# MCU.net
KiCad netlist of a schematic drawn in Altium Designer
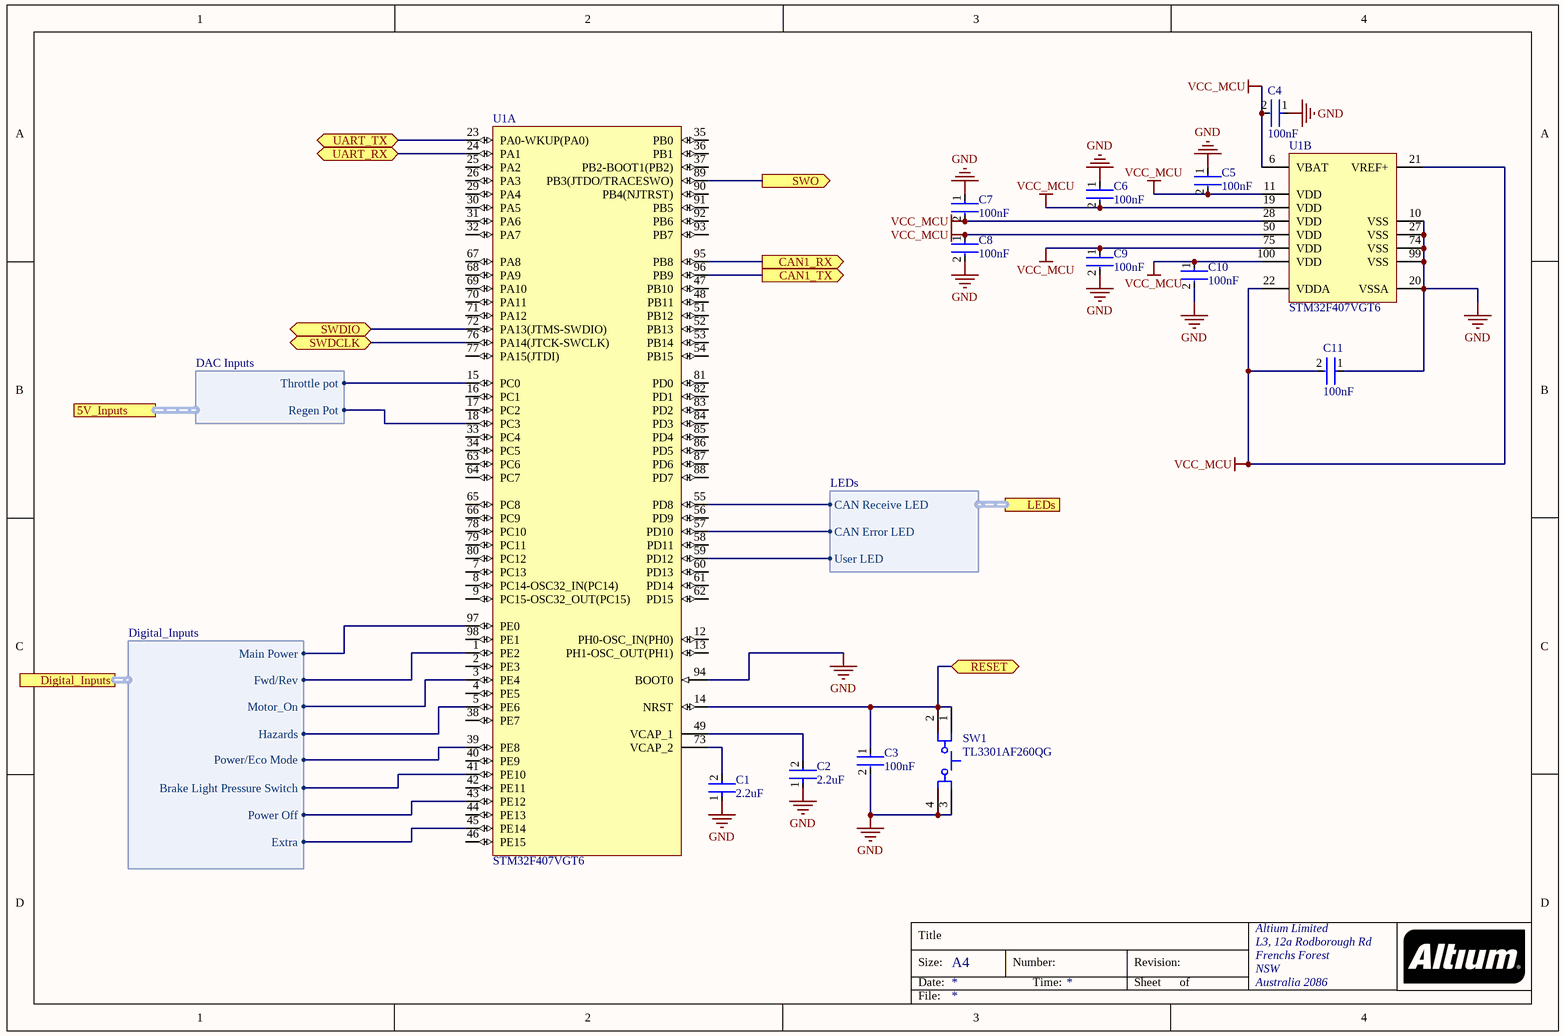
[diagram p0: MCU.SchDoc]

(export (version "E")
  (design (tool "Eeschema 10.0.6"))
  (components
    (comp (ref "C1")
      (value "2.2uF")
      (footprint "Yageo_CC0805-0.85_IPC_A")
      (description "2.2UF CC0805KKX7R6BB225")
      (libsource (lib "Cap_Yageo_CC0805KKX7R6BB225_eec") (part "CC0805KKX7R6BB225"))
    )
    (comp (ref "C2")
      (value "2.2uF")
      (footprint "Yageo_CC0805-0.85_IPC_A")
      (description "2.2UF CC0805KKX7R6BB225")
      (libsource (lib "Cap_Yageo_CC0805KKX7R6BB225_eec") (part "CC0805KKX7R6BB225"))
    )
    (comp (ref "C3")
      (value "100nF")
      (footprint "Kemet_C0603_IPC_A")
      (description "CAP CER 0.1UF 100NF 50V X7R 0603 C0603C104K5RACTU")
      (libsource (lib "UNK_Kemet_C0603C104K5RACTU_eec") (part "C0603C104K5RACTU"))
    )
    (comp (ref "C4")
      (value "100nF")
      (footprint "Kemet_C0603_IPC_A")
      (description "CAP CER 0.1UF 100NF 50V X7R 0603 C0603C104K5RACTU")
      (libsource (lib "UNK_Kemet_C0603C104K5RACTU_eec") (part "C0603C104K5RACTU"))
    )
    (comp (ref "C5")
      (value "100nF")
      (footprint "Kemet_C0603_IPC_A")
      (description "CAP CER 0.1UF 100NF 50V X7R 0603 C0603C104K5RACTU")
      (libsource (lib "UNK_Kemet_C0603C104K5RACTU_eec") (part "C0603C104K5RACTU"))
    )
    (comp (ref "C6")
      (value "100nF")
      (footprint "Kemet_C0603_IPC_A")
      (description "CAP CER 0.1UF 100NF 50V X7R 0603 C0603C104K5RACTU")
      (libsource (lib "UNK_Kemet_C0603C104K5RACTU_eec") (part "C0603C104K5RACTU"))
    )
    (comp (ref "C7")
      (value "100nF")
      (footprint "Kemet_C0603_IPC_A")
      (description "CAP CER 0.1UF 100NF 50V X7R 0603 C0603C104K5RACTU")
      (libsource (lib "UNK_Kemet_C0603C104K5RACTU_eec") (part "C0603C104K5RACTU"))
    )
    (comp (ref "C8")
      (value "100nF")
      (footprint "Kemet_C0603_IPC_A")
      (description "CAP CER 0.1UF 100NF 50V X7R 0603 C0603C104K5RACTU")
      (libsource (lib "UNK_Kemet_C0603C104K5RACTU_eec") (part "C0603C104K5RACTU"))
    )
    (comp (ref "C9")
      (value "100nF")
      (footprint "Kemet_C0603_IPC_A")
      (description "CAP CER 0.1UF 100NF 50V X7R 0603 C0603C104K5RACTU")
      (libsource (lib "UNK_Kemet_C0603C104K5RACTU_eec") (part "C0603C104K5RACTU"))
    )
    (comp (ref "C10")
      (value "100nF")
      (footprint "Kemet_C0603_IPC_A")
      (description "CAP CER 0.1UF 100NF 50V X7R 0603 C0603C104K5RACTU")
      (libsource (lib "UNK_Kemet_C0603C104K5RACTU_eec") (part "C0603C104K5RACTU"))
    )
    (comp (ref "C11")
      (value "100nF")
      (footprint "Kemet_C0603_IPC_A")
      (description "CAP CER 0.1UF 100NF 50V X7R 0603 C0603C104K5RACTU")
      (libsource (lib "UNK_Kemet_C0603C104K5RACTU_eec") (part "C0603C104K5RACTU"))
    )
    (comp (ref "SW1")
      (value "TL3301AF260QG")
      (footprint "ESWI-TL3301AF260QG_V")
      (description "Tactile Switch, SPST-NO, 50 mA, 12 V, -20 to 70 degC, 4-Pin SMD, RoHS, Tape and Reel")
      (fields (field (name "MANUFACTURER") "E-Switch"))
      (libsource (lib "Altium Content Vault") (part "SW-SPST-NO-4"))
    )
    (comp (ref "U1")
      (value "STM32F407VGT6")
      (footprint "STM-LQFP100_M")
      (fields (field (name "MANUFACTURER") "STMicroelectronics"))
      (libsource (lib "Altium Content Vault") (part "MC-ARM-STM32F40X_41X-SQ100"))
    )
  )
  (nets
    (net (code "5") (name "/Brake Light Pressure Switch") (class "Default")
      (node (ref "U1") (pin "41") (pinfunction "PE10_41") (pintype "bidirectional"))
    )
    (net (code "6") (name "/CAN Error LED") (class "Default")
      (node (ref "U1") (pin "57") (pinfunction "PD10_57") (pintype "bidirectional"))
    )
    (net (code "7") (name "/CAN Receive LED") (class "Default")
      (node (ref "U1") (pin "55") (pinfunction "PD8_55") (pintype "bidirectional"))
    )
    (net (code "8") (name "/CAN1_RX") (class "Default")
      (node (ref "U1") (pin "95") (pinfunction "PB8_95") (pintype "bidirectional"))
    )
    (net (code "9") (name "/CAN1_TX") (class "Default")
      (node (ref "U1") (pin "96") (pinfunction "PB9_96") (pintype "bidirectional"))
    )
    (net (code "10") (name "/Extra") (class "Default")
      (node (ref "U1") (pin "45") (pinfunction "PE14_45") (pintype "bidirectional"))
    )
    (net (code "11") (name "/Fwd{slash}Rev") (class "Default")
      (node (ref "U1") (pin "1") (pinfunction "PE2_1") (pintype "bidirectional"))
    )
    (net (code "12") (name "/Hazards") (class "Default")
      (node (ref "U1") (pin "5") (pinfunction "PE6_5") (pintype "bidirectional"))
    )
    (net (code "13") (name "/Main Power") (class "Default")
      (node (ref "U1") (pin "97") (pinfunction "PE0_97") (pintype "bidirectional"))
    )
    (net (code "14") (name "/Motor_On") (class "Default")
      (node (ref "U1") (pin "3") (pinfunction "PE4_3") (pintype "bidirectional"))
    )
    (net (code "15") (name "/Power Off") (class "Default")
      (node (ref "U1") (pin "43") (pinfunction "PE12_43") (pintype "bidirectional"))
    )
    (net (code "16") (name "/Power{slash}Eco Mode") (class "Default")
      (node (ref "U1") (pin "39") (pinfunction "PE8_39") (pintype "bidirectional"))
    )
    (net (code "17") (name "/RESET") (class "Default")
      (node (ref "C3") (pin "1") (pinfunction "1_1") (pintype "passive"))
      (node (ref "SW1") (pin "1") (pinfunction "1_1") (pintype "passive"))
      (node (ref "SW1") (pin "2") (pinfunction "2_2") (pintype "passive"))
      (node (ref "U1") (pin "14") (pinfunction "NRST_14") (pintype "bidirectional"))
    )
    (net (code "18") (name "/Regen Pot") (class "Default")
      (node (ref "U1") (pin "18") (pinfunction "PC3_18") (pintype "bidirectional"))
    )
    (net (code "19") (name "/SWDCLK") (class "Default")
      (node (ref "U1") (pin "76") (pinfunction "PA14(JTCK-SWCLK)_76") (pintype "bidirectional"))
    )
    (net (code "20") (name "/SWDIO") (class "Default")
      (node (ref "U1") (pin "72") (pinfunction "PA13(JTMS-SWDIO)_72") (pintype "bidirectional"))
    )
    (net (code "21") (name "/SWO") (class "Default")
      (node (ref "U1") (pin "89") (pinfunction "PB3(JTDO/TRACESWO)_89") (pintype "bidirectional"))
    )
    (net (code "22") (name "/Throttle pot") (class "Default")
      (node (ref "U1") (pin "15") (pinfunction "PC0_15") (pintype "bidirectional"))
    )
    (net (code "23") (name "/UART_RX") (class "Default")
      (node (ref "U1") (pin "24") (pinfunction "PA1_24") (pintype "bidirectional"))
    )
    (net (code "24") (name "/UART_TX") (class "Default")
      (node (ref "U1") (pin "23") (pinfunction "PA0-WKUP(PA0)_23") (pintype "bidirectional"))
    )
    (net (code "25") (name "/User LED") (class "Default")
      (node (ref "U1") (pin "59") (pinfunction "PD12_59") (pintype "bidirectional"))
    )
    (net (code "29") (name "GND") (class "Default")
      (node (ref "C1") (pin "1") (pinfunction "1_1") (pintype "passive"))
      (node (ref "C10") (pin "2") (pinfunction "2_2") (pintype "passive"))
      (node (ref "C11") (pin "1") (pinfunction "1_1") (pintype "passive"))
      (node (ref "C2") (pin "1") (pinfunction "1_1") (pintype "passive"))
      (node (ref "C3") (pin "2") (pinfunction "2_2") (pintype "passive"))
      (node (ref "C4") (pin "1") (pinfunction "1_1") (pintype "passive"))
      (node (ref "C5") (pin "1") (pinfunction "1_1") (pintype "passive"))
      (node (ref "C6") (pin "1") (pinfunction "1_1") (pintype "passive"))
      (node (ref "C7") (pin "1") (pinfunction "1_1") (pintype "passive"))
      (node (ref "C8") (pin "2") (pinfunction "2_2") (pintype "passive"))
      (node (ref "C9") (pin "2") (pinfunction "2_2") (pintype "passive"))
      (node (ref "SW1") (pin "3") (pinfunction "3_3") (pintype "passive"))
      (node (ref "SW1") (pin "4") (pinfunction "4_4") (pintype "passive"))
      (node (ref "U1") (pin "10") (pinfunction "VSS_10") (pintype "power_in"))
      (node (ref "U1") (pin "20") (pinfunction "VSSA_20") (pintype "power_in"))
      (node (ref "U1") (pin "27") (pinfunction "VSS_27") (pintype "power_in"))
      (node (ref "U1") (pin "74") (pinfunction "VSS_74") (pintype "power_in"))
      (node (ref "U1") (pin "94") (pinfunction "BOOT0_94") (pintype "input"))
      (node (ref "U1") (pin "99") (pinfunction "VSS_99") (pintype "power_in"))
    )
    (net (code "30") (name "Net-(U1A-VCAP_1)") (class "Default")
      (node (ref "C2") (pin "2") (pinfunction "2_2") (pintype "passive"))
      (node (ref "U1") (pin "49") (pinfunction "VCAP_1_49") (pintype "power_in"))
    )
    (net (code "31") (name "Net-(U1A-VCAP_2)") (class "Default")
      (node (ref "C1") (pin "2") (pinfunction "2_2") (pintype "passive"))
      (node (ref "U1") (pin "73") (pinfunction "VCAP_2_73") (pintype "power_in"))
    )
    (net (code "32") (name "VCC_MCU") (class "Default")
      (node (ref "C10") (pin "1") (pinfunction "1_1") (pintype "passive"))
      (node (ref "C11") (pin "2") (pinfunction "2_2") (pintype "passive"))
      (node (ref "C4") (pin "2") (pinfunction "2_2") (pintype "passive"))
      (node (ref "C5") (pin "2") (pinfunction "2_2") (pintype "passive"))
      (node (ref "C6") (pin "2") (pinfunction "2_2") (pintype "passive"))
      (node (ref "C7") (pin "2") (pinfunction "2_2") (pintype "passive"))
      (node (ref "C8") (pin "1") (pinfunction "1_1") (pintype "passive"))
      (node (ref "C9") (pin "1") (pinfunction "1_1") (pintype "passive"))
      (node (ref "U1") (pin "100") (pinfunction "VDD_100") (pintype "power_in"))
      (node (ref "U1") (pin "11") (pinfunction "VDD_11") (pintype "power_in"))
      (node (ref "U1") (pin "19") (pinfunction "VDD_19") (pintype "power_in"))
      (node (ref "U1") (pin "21") (pinfunction "VREF+_21") (pintype "power_in"))
      (node (ref "U1") (pin "22") (pinfunction "VDDA_22") (pintype "power_in"))
      (node (ref "U1") (pin "28") (pinfunction "VDD_28") (pintype "power_in"))
      (node (ref "U1") (pin "50") (pinfunction "VDD_50") (pintype "power_in"))
      (node (ref "U1") (pin "6") (pinfunction "VBAT_6") (pintype "power_in"))
      (node (ref "U1") (pin "75") (pinfunction "VDD_75") (pintype "power_in"))
    )
    (net (code "33") (name "unconnected-(U1A-PA2-Pad25)") (class "Default")
      (node (ref "U1") (pin "25") (pinfunction "PA2_25") (pintype "bidirectional"))
    )
    (net (code "34") (name "unconnected-(U1A-PA3-Pad26)") (class "Default")
      (node (ref "U1") (pin "26") (pinfunction "PA3_26") (pintype "bidirectional"))
    )
    (net (code "35") (name "unconnected-(U1A-PA4-Pad29)") (class "Default")
      (node (ref "U1") (pin "29") (pinfunction "PA4_29") (pintype "bidirectional"))
    )
    (net (code "36") (name "unconnected-(U1A-PA5-Pad30)") (class "Default")
      (node (ref "U1") (pin "30") (pinfunction "PA5_30") (pintype "bidirectional"))
    )
    (net (code "37") (name "unconnected-(U1A-PA6-Pad31)") (class "Default")
      (node (ref "U1") (pin "31") (pinfunction "PA6_31") (pintype "bidirectional"))
    )
    (net (code "38") (name "unconnected-(U1A-PA7-Pad32)") (class "Default")
      (node (ref "U1") (pin "32") (pinfunction "PA7_32") (pintype "bidirectional"))
    )
    (net (code "39") (name "unconnected-(U1A-PA8-Pad67)") (class "Default")
      (node (ref "U1") (pin "67") (pinfunction "PA8_67") (pintype "bidirectional"))
    )
    (net (code "40") (name "unconnected-(U1A-PA9-Pad68)") (class "Default")
      (node (ref "U1") (pin "68") (pinfunction "PA9_68") (pintype "bidirectional"))
    )
    (net (code "41") (name "unconnected-(U1A-PA10-Pad69)") (class "Default")
      (node (ref "U1") (pin "69") (pinfunction "PA10_69") (pintype "bidirectional"))
    )
    (net (code "42") (name "unconnected-(U1A-PA11-Pad70)") (class "Default")
      (node (ref "U1") (pin "70") (pinfunction "PA11_70") (pintype "bidirectional"))
    )
    (net (code "43") (name "unconnected-(U1A-PA12-Pad71)") (class "Default")
      (node (ref "U1") (pin "71") (pinfunction "PA12_71") (pintype "bidirectional"))
    )
    (net (code "44") (name "unconnected-(U1A-PA15(JTDI)-Pad77)") (class "Default")
      (node (ref "U1") (pin "77") (pinfunction "PA15(JTDI)_77") (pintype "bidirectional"))
    )
    (net (code "45") (name "unconnected-(U1A-PB0-Pad35)") (class "Default")
      (node (ref "U1") (pin "35") (pinfunction "PB0_35") (pintype "bidirectional"))
    )
    (net (code "46") (name "unconnected-(U1A-PB1-Pad36)") (class "Default")
      (node (ref "U1") (pin "36") (pinfunction "PB1_36") (pintype "bidirectional"))
    )
    (net (code "47") (name "unconnected-(U1A-PB2-BOOT1(PB2)-Pad37)") (class "Default")
      (node (ref "U1") (pin "37") (pinfunction "PB2-BOOT1(PB2)_37") (pintype "bidirectional"))
    )
    (net (code "48") (name "unconnected-(U1A-PB4(NJTRST)-Pad90)") (class "Default")
      (node (ref "U1") (pin "90") (pinfunction "PB4(NJTRST)_90") (pintype "bidirectional"))
    )
    (net (code "49") (name "unconnected-(U1A-PB5-Pad91)") (class "Default")
      (node (ref "U1") (pin "91") (pinfunction "PB5_91") (pintype "bidirectional"))
    )
    (net (code "50") (name "unconnected-(U1A-PB6-Pad92)") (class "Default")
      (node (ref "U1") (pin "92") (pinfunction "PB6_92") (pintype "bidirectional"))
    )
    (net (code "51") (name "unconnected-(U1A-PB7-Pad93)") (class "Default")
      (node (ref "U1") (pin "93") (pinfunction "PB7_93") (pintype "bidirectional"))
    )
    (net (code "52") (name "unconnected-(U1A-PB10-Pad47)") (class "Default")
      (node (ref "U1") (pin "47") (pinfunction "PB10_47") (pintype "bidirectional"))
    )
    (net (code "53") (name "unconnected-(U1A-PB11-Pad48)") (class "Default")
      (node (ref "U1") (pin "48") (pinfunction "PB11_48") (pintype "bidirectional"))
    )
    (net (code "54") (name "unconnected-(U1A-PB12-Pad51)") (class "Default")
      (node (ref "U1") (pin "51") (pinfunction "PB12_51") (pintype "bidirectional"))
    )
    (net (code "55") (name "unconnected-(U1A-PB13-Pad52)") (class "Default")
      (node (ref "U1") (pin "52") (pinfunction "PB13_52") (pintype "bidirectional"))
    )
    (net (code "56") (name "unconnected-(U1A-PB14-Pad53)") (class "Default")
      (node (ref "U1") (pin "53") (pinfunction "PB14_53") (pintype "bidirectional"))
    )
    (net (code "57") (name "unconnected-(U1A-PB15-Pad54)") (class "Default")
      (node (ref "U1") (pin "54") (pinfunction "PB15_54") (pintype "bidirectional"))
    )
    (net (code "58") (name "unconnected-(U1A-PC1-Pad16)") (class "Default")
      (node (ref "U1") (pin "16") (pinfunction "PC1_16") (pintype "bidirectional"))
    )
    (net (code "59") (name "unconnected-(U1A-PC2-Pad17)") (class "Default")
      (node (ref "U1") (pin "17") (pinfunction "PC2_17") (pintype "bidirectional"))
    )
    (net (code "60") (name "unconnected-(U1A-PC4-Pad33)") (class "Default")
      (node (ref "U1") (pin "33") (pinfunction "PC4_33") (pintype "bidirectional"))
    )
    (net (code "61") (name "unconnected-(U1A-PC5-Pad34)") (class "Default")
      (node (ref "U1") (pin "34") (pinfunction "PC5_34") (pintype "bidirectional"))
    )
    (net (code "62") (name "unconnected-(U1A-PC6-Pad63)") (class "Default")
      (node (ref "U1") (pin "63") (pinfunction "PC6_63") (pintype "bidirectional"))
    )
    (net (code "63") (name "unconnected-(U1A-PC7-Pad64)") (class "Default")
      (node (ref "U1") (pin "64") (pinfunction "PC7_64") (pintype "bidirectional"))
    )
    (net (code "64") (name "unconnected-(U1A-PC8-Pad65)") (class "Default")
      (node (ref "U1") (pin "65") (pinfunction "PC8_65") (pintype "bidirectional"))
    )
    (net (code "65") (name "unconnected-(U1A-PC9-Pad66)") (class "Default")
      (node (ref "U1") (pin "66") (pinfunction "PC9_66") (pintype "bidirectional"))
    )
    (net (code "66") (name "unconnected-(U1A-PC10-Pad78)") (class "Default")
      (node (ref "U1") (pin "78") (pinfunction "PC10_78") (pintype "bidirectional"))
    )
    (net (code "67") (name "unconnected-(U1A-PC11-Pad79)") (class "Default")
      (node (ref "U1") (pin "79") (pinfunction "PC11_79") (pintype "bidirectional"))
    )
    (net (code "68") (name "unconnected-(U1A-PC12-Pad80)") (class "Default")
      (node (ref "U1") (pin "80") (pinfunction "PC12_80") (pintype "bidirectional"))
    )
    (net (code "69") (name "unconnected-(U1A-PC13-Pad7)") (class "Default")
      (node (ref "U1") (pin "7") (pinfunction "PC13_7") (pintype "bidirectional"))
    )
    (net (code "70") (name "unconnected-(U1A-PC14-OSC32_IN(PC14)-Pad8)") (class "Default")
      (node (ref "U1") (pin "8") (pinfunction "PC14-OSC32_IN(PC14)_8") (pintype "bidirectional"))
    )
    (net (code "71") (name "unconnected-(U1A-PC15-OSC32_OUT(PC15)-Pad9)") (class "Default")
      (node (ref "U1") (pin "9") (pinfunction "PC15-OSC32_OUT(PC15)_9") (pintype "bidirectional"))
    )
    (net (code "72") (name "unconnected-(U1A-PD0-Pad81)") (class "Default")
      (node (ref "U1") (pin "81") (pinfunction "PD0_81") (pintype "bidirectional"))
    )
    (net (code "73") (name "unconnected-(U1A-PD1-Pad82)") (class "Default")
      (node (ref "U1") (pin "82") (pinfunction "PD1_82") (pintype "bidirectional"))
    )
    (net (code "74") (name "unconnected-(U1A-PD2-Pad83)") (class "Default")
      (node (ref "U1") (pin "83") (pinfunction "PD2_83") (pintype "bidirectional"))
    )
    (net (code "75") (name "unconnected-(U1A-PD3-Pad84)") (class "Default")
      (node (ref "U1") (pin "84") (pinfunction "PD3_84") (pintype "bidirectional"))
    )
    (net (code "76") (name "unconnected-(U1A-PD4-Pad85)") (class "Default")
      (node (ref "U1") (pin "85") (pinfunction "PD4_85") (pintype "bidirectional"))
    )
    (net (code "77") (name "unconnected-(U1A-PD5-Pad86)") (class "Default")
      (node (ref "U1") (pin "86") (pinfunction "PD5_86") (pintype "bidirectional"))
    )
    (net (code "78") (name "unconnected-(U1A-PD6-Pad87)") (class "Default")
      (node (ref "U1") (pin "87") (pinfunction "PD6_87") (pintype "bidirectional"))
    )
    (net (code "79") (name "unconnected-(U1A-PD7-Pad88)") (class "Default")
      (node (ref "U1") (pin "88") (pinfunction "PD7_88") (pintype "bidirectional"))
    )
    (net (code "80") (name "unconnected-(U1A-PD9-Pad56)") (class "Default")
      (node (ref "U1") (pin "56") (pinfunction "PD9_56") (pintype "bidirectional"))
    )
    (net (code "81") (name "unconnected-(U1A-PD11-Pad58)") (class "Default")
      (node (ref "U1") (pin "58") (pinfunction "PD11_58") (pintype "bidirectional"))
    )
    (net (code "82") (name "unconnected-(U1A-PD13-Pad60)") (class "Default")
      (node (ref "U1") (pin "60") (pinfunction "PD13_60") (pintype "bidirectional"))
    )
    (net (code "83") (name "unconnected-(U1A-PD14-Pad61)") (class "Default")
      (node (ref "U1") (pin "61") (pinfunction "PD14_61") (pintype "bidirectional"))
    )
    (net (code "84") (name "unconnected-(U1A-PD15-Pad62)") (class "Default")
      (node (ref "U1") (pin "62") (pinfunction "PD15_62") (pintype "bidirectional"))
    )
    (net (code "85") (name "unconnected-(U1A-PE1-Pad98)") (class "Default")
      (node (ref "U1") (pin "98") (pinfunction "PE1_98") (pintype "bidirectional"))
    )
    (net (code "86") (name "unconnected-(U1A-PE3-Pad2)") (class "Default")
      (node (ref "U1") (pin "2") (pinfunction "PE3_2") (pintype "bidirectional"))
    )
    (net (code "87") (name "unconnected-(U1A-PE5-Pad4)") (class "Default")
      (node (ref "U1") (pin "4") (pinfunction "PE5_4") (pintype "bidirectional"))
    )
    (net (code "88") (name "unconnected-(U1A-PE7-Pad38)") (class "Default")
      (node (ref "U1") (pin "38") (pinfunction "PE7_38") (pintype "bidirectional"))
    )
    (net (code "89") (name "unconnected-(U1A-PE9-Pad40)") (class "Default")
      (node (ref "U1") (pin "40") (pinfunction "PE9_40") (pintype "bidirectional"))
    )
    (net (code "90") (name "unconnected-(U1A-PE11-Pad42)") (class "Default")
      (node (ref "U1") (pin "42") (pinfunction "PE11_42") (pintype "bidirectional"))
    )
    (net (code "91") (name "unconnected-(U1A-PE13-Pad44)") (class "Default")
      (node (ref "U1") (pin "44") (pinfunction "PE13_44") (pintype "bidirectional"))
    )
    (net (code "92") (name "unconnected-(U1A-PE15-Pad46)") (class "Default")
      (node (ref "U1") (pin "46") (pinfunction "PE15_46") (pintype "bidirectional"))
    )
    (net (code "93") (name "unconnected-(U1A-PH0-OSC_IN(PH0)-Pad12)") (class "Default")
      (node (ref "U1") (pin "12") (pinfunction "PH0-OSC_IN(PH0)_12") (pintype "bidirectional"))
    )
    (net (code "94") (name "unconnected-(U1A-PH1-OSC_OUT(PH1)-Pad13)") (class "Default")
      (node (ref "U1") (pin "13") (pinfunction "PH1-OSC_OUT(PH1)_13") (pintype "bidirectional"))
    )
  )
)
